# openSX70-dongle_SEEED_v401.net
KiCad netlist of a schematic drawn in EAGLE
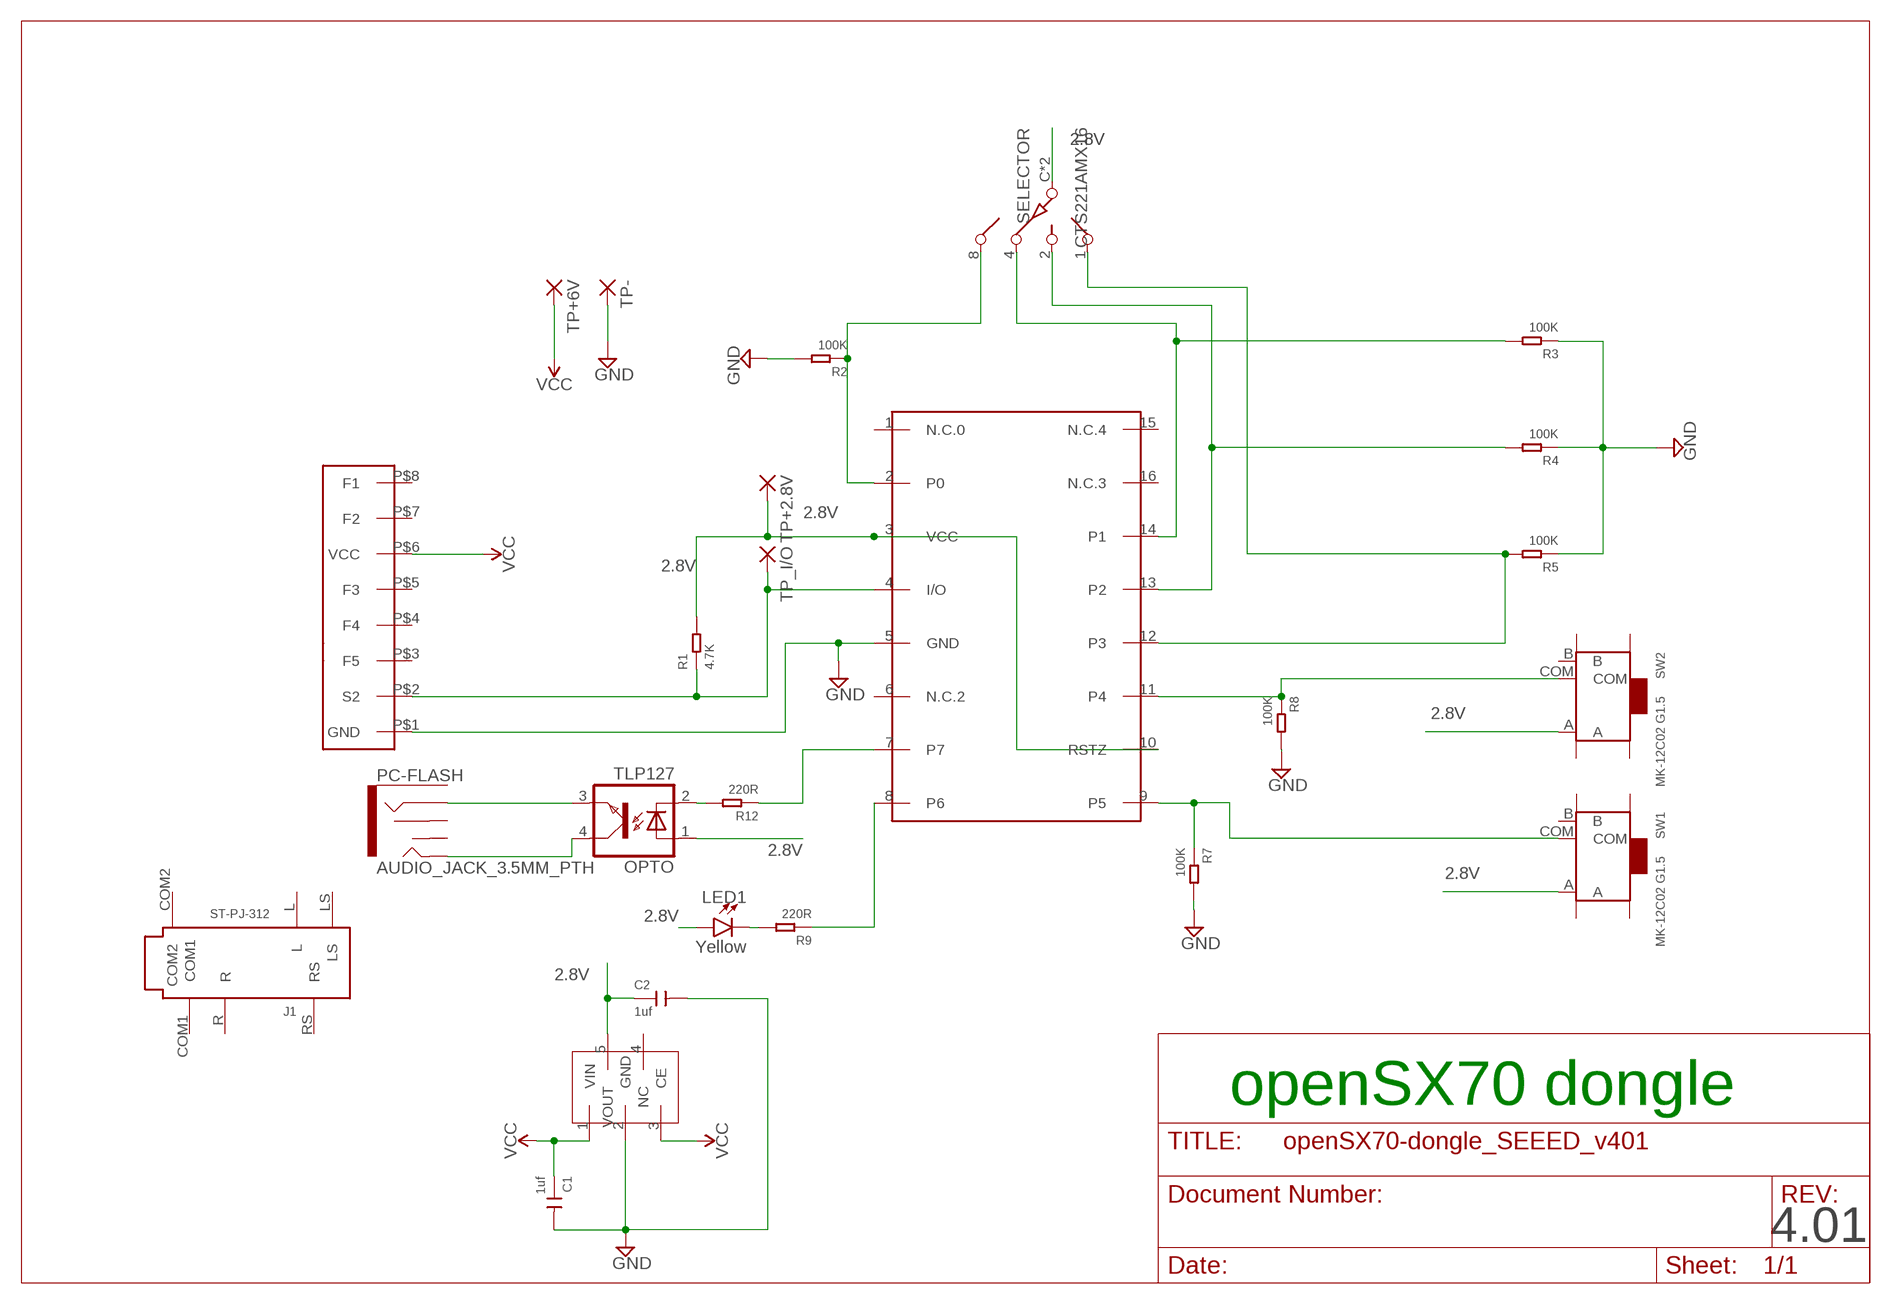
[diagram p0: schematic, sheet 1]

(export (version "E")
  (design (tool "Eeschema 10.0.6"))
  (components
    (comp (ref "C1")
      (value "1uf")
      (footprint "eagle-import:C0603")
      (fields (field (name "MPN") "CC0603KRX7R8BB105"))
      (libsource (lib "eagle-import") (part "CERAMIC-1UF-25V-10%-X7R(0603)"))
    )
    (comp (ref "C2")
      (value "1uf")
      (footprint "eagle-import:C0603")
      (fields (field (name "MPN") "CC0603KRX7R8BB105"))
      (libsource (lib "eagle-import") (part "CERAMIC-1UF-25V-10%-X7R(0603)"))
    )
    (comp (ref "DS2408")
      (value "DS2408")
      (footprint "eagle-import:SO16")
      (libsource (lib "eagle-import") (part "DS2408"))
    )
    (comp (ref "J1")
      (value "ST-PJ-312")
      (footprint "eagle-import:AUDIO6P-SMD-3.5-14.0X6.4X5.0MM")
      (libsource (lib "eagle-import") (part "AUDIO-JACK-6P-SMD(ST-PJ-312)"))
    )
    (comp (ref "LED1")
      (value "Yellow")
      (footprint "eagle-import:LED-1206")
      (libsource (lib "eagle-import") (part "LED-YELLOWLILYPAD"))
    )
    (comp (ref "OPTO")
      (value "TLP127")
      (footprint "eagle-import:SO-4")
      (libsource (lib "eagle-import") (part "TLP127"))
    )
    (comp (ref "PC-FLASH")
      (value "AUDIO_JACK_3.5MM_PTH")
      (footprint "eagle-import:AUDIO-JACK")
      (libsource (lib "eagle-import") (part "AUDIO_JACK_3.5MM_PTH"))
    )
    (comp (ref "R1")
      (value "4.7K")
      (footprint "eagle-import:R0603")
      (fields (field (name "MPN") "RC0603JR-074K7L"))
      (libsource (lib "eagle-import") (part "SMD-RES-4.7K-5%-1/10W(0603)"))
    )
    (comp (ref "R2")
      (value "100K")
      (footprint "eagle-import:R0603")
      (fields (field (name "MPN") "RC0603FR-07100KL"))
      (libsource (lib "eagle-import") (part "SMD-RES-100K-1%-1/10W(0603)"))
    )
    (comp (ref "R3")
      (value "100K")
      (footprint "eagle-import:R0603")
      (fields (field (name "MPN") "RC0603FR-07100KL"))
      (libsource (lib "eagle-import") (part "SMD-RES-100K-1%-1/10W(0603)"))
    )
    (comp (ref "R4")
      (value "100K")
      (footprint "eagle-import:R0603")
      (fields (field (name "MPN") "RC0603FR-07100KL"))
      (libsource (lib "eagle-import") (part "SMD-RES-100K-1%-1/10W(0603)"))
    )
    (comp (ref "R5")
      (value "100K")
      (footprint "eagle-import:R0603")
      (fields (field (name "MPN") "RC0603FR-07100KL"))
      (libsource (lib "eagle-import") (part "SMD-RES-100K-1%-1/10W(0603)"))
    )
    (comp (ref "R7")
      (value "100K")
      (footprint "eagle-import:R0603")
      (fields (field (name "MPN") "RC0603FR-07100KL"))
      (libsource (lib "eagle-import") (part "SMD-RES-100K-1%-1/10W(0603)"))
    )
    (comp (ref "R8")
      (value "100K")
      (footprint "eagle-import:R0603")
      (fields (field (name "MPN") "RC0603FR-07100KL"))
      (libsource (lib "eagle-import") (part "SMD-RES-100K-1%-1/10W(0603)"))
    )
    (comp (ref "R9")
      (value "220R")
      (footprint "eagle-import:R0603")
      (fields (field (name "MPN") "RC0603JR-07220RL"))
      (libsource (lib "eagle-import") (part "SMD-RES-220R-5%-1/10W(0603)"))
    )
    (comp (ref "R12")
      (value "220R")
      (footprint "eagle-import:R0603")
      (fields (field (name "MPN") "RC0603JR-07220RL"))
      (libsource (lib "eagle-import") (part "SMD-RES-220R-5%-1/10W(0603)"))
    )
    (comp (ref "REG")
      (value "NCP4688")
      (footprint "eagle-import:SOT-23-5")
      (libsource (lib "eagle-import") (part "NCP4688"))
    )
    (comp (ref "SELECTOR")
      (value "CTS221AMX16")
      (footprint "eagle-import:CTS221AMX16")
      (libsource (lib "eagle-import") (part "CTS221AMX16"))
    )
    (comp (ref "SW1")
      (value "MK-12C02 G1.5")
      (footprint "eagle-import:SW7-SMD-L6.7X2.7X3.2MM")
      (libsource (lib "eagle-import") (part "SMD-TOGGLE-SWITCH-ON-ON(3+4P-6.7X2.7MM)"))
    )
    (comp (ref "SW2")
      (value "MK-12C02 G1.5")
      (footprint "eagle-import:SW7-SMD-L6.7X2.7X3.2MM")
      (libsource (lib "eagle-import") (part "SMD-TOGGLE-SWITCH-ON-ON(3+4P-6.7X2.7MM)"))
    )
    (comp (ref "TP+2.8V")
      (value "SMD2")
      (footprint "eagle-import:SMD1,27-2,54")
      (libsource (lib "eagle-import") (part "SMD2"))
    )
    (comp (ref "TP+6V")
      (value "SMD2")
      (footprint "eagle-import:SMD1,27-2,54")
      (libsource (lib "eagle-import") (part "SMD2"))
    )
    (comp (ref "TP-")
      (value "SMD2")
      (footprint "eagle-import:SMD1,27-2,54")
      (libsource (lib "eagle-import") (part "SMD2"))
    )
    (comp (ref "TP_I/O")
      (value "SMD2")
      (footprint "eagle-import:SMD1,27-2,54")
      (libsource (lib "eagle-import") (part "SMD2"))
    )
    (comp (ref "U$1")
      (value "FLASH-EDGE-CONNECTOR")
      (footprint "eagle-import:FLASH-EDGE-8")
      (libsource (lib "eagle-import") (part "FLASH-EDGE-CONNECTOR"))
    )
  )
  (nets
    (net (code "1") (name "/2.8V") (class "Default")
      (node (ref "C2") (pin "1") (pinfunction "1_1") (pintype "passive"))
      (node (ref "DS2408") (pin "10") (pinfunction "RSTZ_10") (pintype "bidirectional"))
      (node (ref "DS2408") (pin "3") (pinfunction "VCC_3") (pintype "bidirectional"))
      (node (ref "LED1") (pin "A") (pinfunction "A_A") (pintype "passive"))
      (node (ref "OPTO") (pin "1") (pinfunction "A_1") (pintype "passive"))
      (node (ref "R1") (pin "2") (pinfunction "2_2") (pintype "passive"))
      (node (ref "REG") (pin "5") (pinfunction "VOUT_5") (pintype "bidirectional"))
      (node (ref "SELECTOR") (pin "C") (pinfunction "C_C") (pintype "passive"))
      (node (ref "SELECTOR") (pin "C2") (pinfunction "C_C2") (pintype "passive"))
      (node (ref "SW1") (pin "A") (pinfunction "A_A") (pintype "bidirectional"))
      (node (ref "SW2") (pin "A") (pinfunction "A_A") (pintype "bidirectional"))
      (node (ref "TP+2.8V") (pin "1") (pinfunction "P_1") (pintype "passive"))
    )
    (net (code "2") (name "GND") (class "Default")
      (node (ref "C1") (pin "2") (pinfunction "2_2") (pintype "passive"))
      (node (ref "C2") (pin "2") (pinfunction "2_2") (pintype "passive"))
      (node (ref "DS2408") (pin "5") (pinfunction "GND_5") (pintype "bidirectional"))
      (node (ref "R2") (pin "2") (pinfunction "2_2") (pintype "passive"))
      (node (ref "R3") (pin "1") (pinfunction "1_1") (pintype "passive"))
      (node (ref "R4") (pin "1") (pinfunction "1_1") (pintype "passive"))
      (node (ref "R5") (pin "1") (pinfunction "1_1") (pintype "passive"))
      (node (ref "R7") (pin "2") (pinfunction "2_2") (pintype "passive"))
      (node (ref "R8") (pin "2") (pinfunction "2_2") (pintype "passive"))
      (node (ref "REG") (pin "2") (pinfunction "GND_2") (pintype "bidirectional"))
      (node (ref "TP-") (pin "1") (pinfunction "P_1") (pintype "passive"))
      (node (ref "U$1") (pin "P$1") (pinfunction "GND_P$1") (pintype "bidirectional"))
    )
    (net (code "3") (name "Net-(DS2408-I{slash}O)") (class "Default")
      (node (ref "DS2408") (pin "4") (pinfunction "I/O_4") (pintype "bidirectional"))
      (node (ref "R1") (pin "1") (pinfunction "1_1") (pintype "passive"))
      (node (ref "TP_I/O") (pin "1") (pinfunction "P_1") (pintype "passive"))
      (node (ref "U$1") (pin "P$2") (pinfunction "S2_P$2") (pintype "bidirectional"))
    )
    (net (code "4") (name "Net-(DS2408-P0)") (class "Default")
      (node (ref "DS2408") (pin "2") (pinfunction "P0_2") (pintype "bidirectional"))
      (node (ref "R2") (pin "1") (pinfunction "1_1") (pintype "passive"))
      (node (ref "SELECTOR") (pin "8") (pinfunction "8_8") (pintype "passive"))
    )
    (net (code "5") (name "Net-(DS2408-P1)") (class "Default")
      (node (ref "DS2408") (pin "14") (pinfunction "P1_14") (pintype "bidirectional"))
      (node (ref "R3") (pin "2") (pinfunction "2_2") (pintype "passive"))
      (node (ref "SELECTOR") (pin "4") (pinfunction "4_4") (pintype "passive"))
    )
    (net (code "6") (name "Net-(DS2408-P2)") (class "Default")
      (node (ref "DS2408") (pin "13") (pinfunction "P2_13") (pintype "bidirectional"))
      (node (ref "R4") (pin "2") (pinfunction "2_2") (pintype "passive"))
      (node (ref "SELECTOR") (pin "2") (pinfunction "2_2") (pintype "passive"))
    )
    (net (code "7") (name "Net-(DS2408-P3)") (class "Default")
      (node (ref "DS2408") (pin "12") (pinfunction "P3_12") (pintype "bidirectional"))
      (node (ref "R5") (pin "2") (pinfunction "2_2") (pintype "passive"))
      (node (ref "SELECTOR") (pin "1") (pinfunction "1_1") (pintype "passive"))
    )
    (net (code "8") (name "Net-(DS2408-P4)") (class "Default")
      (node (ref "DS2408") (pin "11") (pinfunction "P4_11") (pintype "bidirectional"))
      (node (ref "R8") (pin "1") (pinfunction "1_1") (pintype "passive"))
      (node (ref "SW2") (pin "COM") (pinfunction "COM_COM") (pintype "bidirectional"))
    )
    (net (code "9") (name "Net-(DS2408-P5)") (class "Default")
      (node (ref "DS2408") (pin "9") (pinfunction "P5_9") (pintype "bidirectional"))
      (node (ref "R7") (pin "1") (pinfunction "1_1") (pintype "passive"))
      (node (ref "SW1") (pin "COM") (pinfunction "COM_COM") (pintype "bidirectional"))
    )
    (net (code "10") (name "Net-(DS2408-P6)") (class "Default")
      (node (ref "DS2408") (pin "8") (pinfunction "P6_8") (pintype "bidirectional"))
      (node (ref "R9") (pin "1") (pinfunction "1_1") (pintype "passive"))
    )
    (net (code "11") (name "Net-(DS2408-P7)") (class "Default")
      (node (ref "DS2408") (pin "7") (pinfunction "P7_7") (pintype "bidirectional"))
      (node (ref "R12") (pin "1") (pinfunction "1_1") (pintype "passive"))
    )
    (net (code "12") (name "Net-(LED1-PadC)") (class "Default")
      (node (ref "LED1") (pin "C") (pinfunction "C_C") (pintype "passive"))
      (node (ref "R9") (pin "2") (pinfunction "2_2") (pintype "passive"))
    )
    (net (code "13") (name "Net-(OPTO-C)") (class "Default")
      (node (ref "OPTO") (pin "2") (pinfunction "C_2") (pintype "passive"))
      (node (ref "R12") (pin "2") (pinfunction "2_2") (pintype "passive"))
    )
    (net (code "14") (name "Net-(OPTO-COL)") (class "Default")
      (node (ref "OPTO") (pin "4") (pinfunction "COL_4") (pintype "passive"))
      (node (ref "PC-FLASH") (pin "TIP") (pinfunction "TIP_TIP") (pintype "bidirectional"))
    )
    (net (code "15") (name "Net-(OPTO-EMIT)") (class "Default")
      (node (ref "OPTO") (pin "3") (pinfunction "EMIT_3") (pintype "passive"))
      (node (ref "PC-FLASH") (pin "RING") (pinfunction "RING_RING") (pintype "bidirectional"))
    )
    (net (code "16") (name "VCC") (class "Default")
      (node (ref "C1") (pin "1") (pinfunction "1_1") (pintype "passive"))
      (node (ref "REG") (pin "1") (pinfunction "VIN_1") (pintype "bidirectional"))
      (node (ref "REG") (pin "3") (pinfunction "CE_3") (pintype "bidirectional"))
      (node (ref "TP+6V") (pin "1") (pinfunction "P_1") (pintype "passive"))
      (node (ref "U$1") (pin "P$6") (pinfunction "VCC_P$6") (pintype "bidirectional"))
    )
    (net (code "17") (name "unconnected-(DS2408-N.C.0-Pad1)") (class "Default")
      (node (ref "DS2408") (pin "1") (pinfunction "N.C.0_1") (pintype "bidirectional"))
    )
    (net (code "18") (name "unconnected-(DS2408-N.C.2-Pad6)") (class "Default")
      (node (ref "DS2408") (pin "6") (pinfunction "N.C.2_6") (pintype "bidirectional"))
    )
    (net (code "19") (name "unconnected-(DS2408-N.C.3-Pad16)") (class "Default")
      (node (ref "DS2408") (pin "16") (pinfunction "N.C.3_16") (pintype "bidirectional"))
    )
    (net (code "20") (name "unconnected-(DS2408-N.C.4-Pad15)") (class "Default")
      (node (ref "DS2408") (pin "15") (pinfunction "N.C.4_15") (pintype "bidirectional"))
    )
    (net (code "21") (name "unconnected-(J1-PadCOM1)") (class "Default")
      (node (ref "J1") (pin "COM1") (pinfunction "COM1_COM1") (pintype "bidirectional"))
    )
    (net (code "22") (name "unconnected-(J1-PadCOM2)") (class "Default")
      (node (ref "J1") (pin "COM2") (pinfunction "COM2_COM2") (pintype "bidirectional"))
    )
    (net (code "23") (name "unconnected-(J1-PadL)") (class "Default")
      (node (ref "J1") (pin "L") (pinfunction "L_L") (pintype "bidirectional"))
    )
    (net (code "24") (name "unconnected-(J1-PadLS)") (class "Default")
      (node (ref "J1") (pin "LS") (pinfunction "LS_LS") (pintype "bidirectional"))
    )
    (net (code "25") (name "unconnected-(J1-PadR)") (class "Default")
      (node (ref "J1") (pin "R") (pinfunction "R_R") (pintype "bidirectional"))
    )
    (net (code "26") (name "unconnected-(J1-PadRS)") (class "Default")
      (node (ref "J1") (pin "RS") (pinfunction "RS_RS") (pintype "bidirectional"))
    )
    (net (code "27") (name "unconnected-(PC-FLASH-PadRSH)") (class "Default")
      (node (ref "PC-FLASH") (pin "RSH") (pinfunction "RSH_RSH") (pintype "bidirectional"))
    )
    (net (code "28") (name "unconnected-(PC-FLASH-PadSLEEVE)") (class "Default")
      (node (ref "PC-FLASH") (pin "SLEEVE") (pinfunction "SLEEVE_SLEEVE") (pintype "bidirectional"))
    )
    (net (code "29") (name "unconnected-(PC-FLASH-PadTSH)") (class "Default")
      (node (ref "PC-FLASH") (pin "TSH") (pinfunction "TSH_TSH") (pintype "bidirectional"))
    )
    (net (code "30") (name "unconnected-(REG-NC-Pad4)") (class "Default")
      (node (ref "REG") (pin "4") (pinfunction "NC_4") (pintype "bidirectional"))
    )
    (net (code "31") (name "unconnected-(SW1-PadB)") (class "Default")
      (node (ref "SW1") (pin "B") (pinfunction "B_B") (pintype "bidirectional"))
    )
    (net (code "32") (name "unconnected-(SW1-PadSS1)") (class "Default")
      (node (ref "SW1") (pin "SS1") (pinfunction "SS1_SS1") (pintype "bidirectional"))
    )
    (net (code "33") (name "unconnected-(SW1-PadSS2)") (class "Default")
      (node (ref "SW1") (pin "SS2") (pinfunction "SS2_SS2") (pintype "bidirectional"))
    )
    (net (code "34") (name "unconnected-(SW1-PadSS3)") (class "Default")
      (node (ref "SW1") (pin "SS3") (pinfunction "SS3_SS3") (pintype "bidirectional"))
    )
    (net (code "35") (name "unconnected-(SW1-PadSS4)") (class "Default")
      (node (ref "SW1") (pin "SS4") (pinfunction "SS4_SS4") (pintype "bidirectional"))
    )
    (net (code "36") (name "unconnected-(SW2-PadB)") (class "Default")
      (node (ref "SW2") (pin "B") (pinfunction "B_B") (pintype "bidirectional"))
    )
    (net (code "37") (name "unconnected-(SW2-PadSS1)") (class "Default")
      (node (ref "SW2") (pin "SS1") (pinfunction "SS1_SS1") (pintype "bidirectional"))
    )
    (net (code "38") (name "unconnected-(SW2-PadSS2)") (class "Default")
      (node (ref "SW2") (pin "SS2") (pinfunction "SS2_SS2") (pintype "bidirectional"))
    )
    (net (code "39") (name "unconnected-(SW2-PadSS3)") (class "Default")
      (node (ref "SW2") (pin "SS3") (pinfunction "SS3_SS3") (pintype "bidirectional"))
    )
    (net (code "40") (name "unconnected-(SW2-PadSS4)") (class "Default")
      (node (ref "SW2") (pin "SS4") (pinfunction "SS4_SS4") (pintype "bidirectional"))
    )
    (net (code "41") (name "unconnected-(U$1-F1-PadP$8)") (class "Default")
      (node (ref "U$1") (pin "P$8") (pinfunction "F1_P$8") (pintype "bidirectional"))
    )
    (net (code "42") (name "unconnected-(U$1-F2-PadP$7)") (class "Default")
      (node (ref "U$1") (pin "P$7") (pinfunction "F2_P$7") (pintype "bidirectional"))
    )
    (net (code "43") (name "unconnected-(U$1-F3-PadP$5)") (class "Default")
      (node (ref "U$1") (pin "P$5") (pinfunction "F3_P$5") (pintype "bidirectional"))
    )
    (net (code "44") (name "unconnected-(U$1-F4-PadP$4)") (class "Default")
      (node (ref "U$1") (pin "P$4") (pinfunction "F4_P$4") (pintype "bidirectional"))
    )
    (net (code "45") (name "unconnected-(U$1-F5-PadP$3)") (class "Default")
      (node (ref "U$1") (pin "P$3") (pinfunction "F5_P$3") (pintype "bidirectional"))
    )
  )
)
